# PCB-PAYLOAD_FINAL.net
KiCad netlist of a schematic drawn in EAGLE
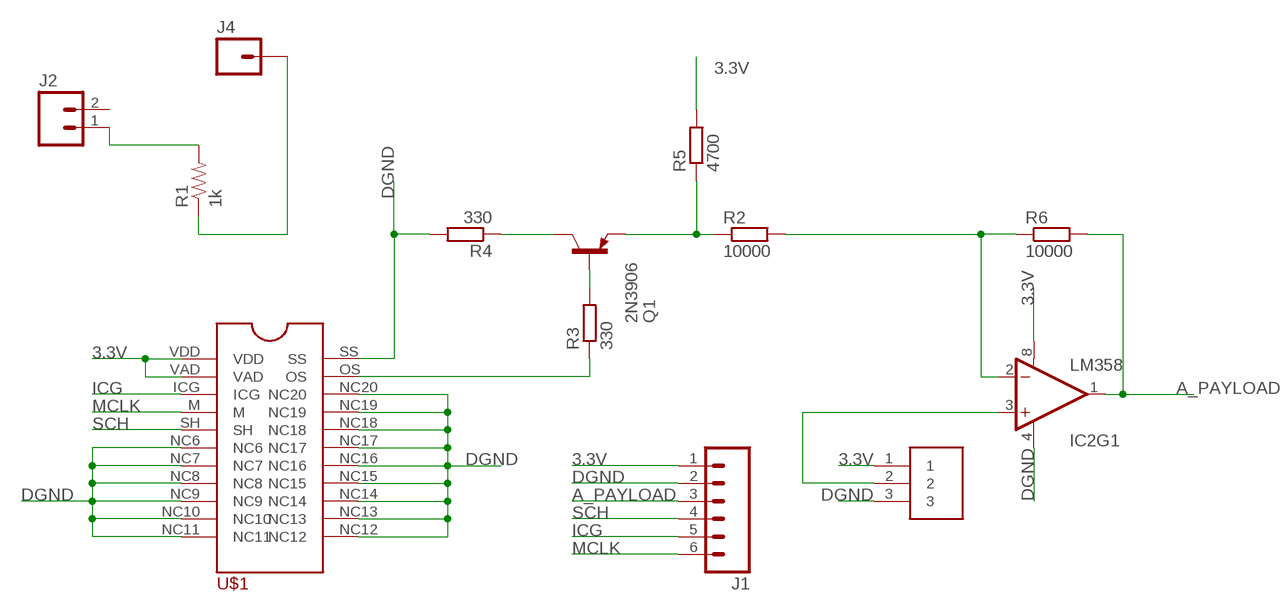
[diagram p0: schematic, sheet 1]

(export (version "E")
  (design (tool "Eeschema 10.0.6"))
  (components
    (comp (ref "IC2")
      (value "LM358")
      (footprint "eagle-import:DIP08")
      (libsource (lib "eagle-import") (part "LM358"))
    )
    (comp (ref "J1")
      (value "M06SILK_FEMALE_PTH")
      (footprint "eagle-import:1X06")
      (libsource (lib "eagle-import") (part "M06SILK_FEMALE_PTH"))
    )
    (comp (ref "J2")
      (value "M02PTH")
      (footprint "eagle-import:1X02")
      (libsource (lib "eagle-import") (part "M02PTH"))
    )
    (comp (ref "J4")
      (value "M01PTH")
      (footprint "eagle-import:1X01")
      (libsource (lib "eagle-import") (part "M01PTH"))
    )
    (comp (ref "Q1")
      (value "2N3906")
      (footprint "eagle-import:TO92")
      (libsource (lib "eagle-import") (part "2N3906"))
    )
    (comp (ref "R1")
      (value "1k")
      (footprint "eagle-import:AXIAL-0.3")
      (libsource (lib "eagle-import") (part "1KOHM-1/4W-5%(PTH)"))
    )
    (comp (ref "R2")
      (value "10000")
      (footprint "eagle-import:0204_5")
      (libsource (lib "eagle-import") (part "R-EU_0204/5"))
    )
    (comp (ref "R3")
      (value "330")
      (footprint "eagle-import:0204_5")
      (libsource (lib "eagle-import") (part "R-EU_0204/5"))
    )
    (comp (ref "R4")
      (value "330")
      (footprint "eagle-import:0204_5")
      (libsource (lib "eagle-import") (part "R-EU_0204/5"))
    )
    (comp (ref "R5")
      (value "4700")
      (footprint "eagle-import:0204_5")
      (libsource (lib "eagle-import") (part "R-EU_0204/5"))
    )
    (comp (ref "R6")
      (value "10000")
      (footprint "eagle-import:0204_5")
      (libsource (lib "eagle-import") (part "R-EU_0204/5"))
    )
    (comp (ref "U$1")
      (value "CCD")
      (footprint "eagle-import:CCD")
      (libsource (lib "eagle-import") (part "CCD"))
    )
    (comp (ref "U$2")
      (value "TRIMPOT_DEVICE")
      (footprint "eagle-import:TRIM_POT_PACKAGE")
      (libsource (lib "eagle-import") (part "TRIMPOT_DEVICE"))
    )
  )
  (nets
    (net (code "1") (name "/3.3V") (class "Default")
      (node (ref "IC2") (pin "8") (pinfunction "V+_8") (pintype "power_in"))
      (node (ref "J1") (pin "1") (pinfunction "1_1") (pintype "passive"))
      (node (ref "R5") (pin "2") (pinfunction "2_2") (pintype "passive"))
      (node (ref "U$1") (pin "VAD") (pinfunction "VAD_VAD") (pintype "bidirectional"))
      (node (ref "U$1") (pin "VDD") (pinfunction "VDD_VDD") (pintype "bidirectional"))
      (node (ref "U$2") (pin "1") (pinfunction "1_1") (pintype "bidirectional"))
    )
    (net (code "2") (name "/A_PAYLOAD") (class "Default")
      (node (ref "IC2") (pin "1") (pinfunction "OUT_1") (pintype "output"))
      (node (ref "J1") (pin "3") (pinfunction "3_3") (pintype "passive"))
      (node (ref "R6") (pin "2") (pinfunction "2_2") (pintype "passive"))
    )
    (net (code "3") (name "/DGND") (class "Default")
      (node (ref "IC2") (pin "4") (pinfunction "V-_4") (pintype "power_in"))
      (node (ref "J1") (pin "2") (pinfunction "2_2") (pintype "passive"))
      (node (ref "R4") (pin "2") (pinfunction "2_2") (pintype "passive"))
      (node (ref "U$1") (pin "NC10") (pinfunction "NC10_NC10") (pintype "bidirectional"))
      (node (ref "U$1") (pin "NC11") (pinfunction "NC11_NC11") (pintype "bidirectional"))
      (node (ref "U$1") (pin "NC12") (pinfunction "NC12_NC12") (pintype "bidirectional"))
      (node (ref "U$1") (pin "NC13") (pinfunction "NC13_NC13") (pintype "bidirectional"))
      (node (ref "U$1") (pin "NC14") (pinfunction "NC14_NC14") (pintype "bidirectional"))
      (node (ref "U$1") (pin "NC15") (pinfunction "NC15_NC15") (pintype "bidirectional"))
      (node (ref "U$1") (pin "NC16") (pinfunction "NC16_NC16") (pintype "bidirectional"))
      (node (ref "U$1") (pin "NC17") (pinfunction "NC17_NC17") (pintype "bidirectional"))
      (node (ref "U$1") (pin "NC18") (pinfunction "NC18_NC18") (pintype "bidirectional"))
      (node (ref "U$1") (pin "NC19") (pinfunction "NC19_NC19") (pintype "bidirectional"))
      (node (ref "U$1") (pin "NC20") (pinfunction "NC20_NC20") (pintype "bidirectional"))
      (node (ref "U$1") (pin "NC6") (pinfunction "NC6_NC6") (pintype "bidirectional"))
      (node (ref "U$1") (pin "NC7") (pinfunction "NC7_NC7") (pintype "bidirectional"))
      (node (ref "U$1") (pin "NC8") (pinfunction "NC8_NC8") (pintype "bidirectional"))
      (node (ref "U$1") (pin "NC9") (pinfunction "NC9_NC9") (pintype "bidirectional"))
      (node (ref "U$1") (pin "SS") (pinfunction "SS_SS") (pintype "bidirectional"))
      (node (ref "U$2") (pin "3") (pinfunction "3_3") (pintype "bidirectional"))
    )
    (net (code "4") (name "/ICG") (class "Default")
      (node (ref "J1") (pin "5") (pinfunction "5_5") (pintype "passive"))
      (node (ref "U$1") (pin "ICG") (pinfunction "ICG_ICG") (pintype "bidirectional"))
    )
    (net (code "5") (name "/MCLK") (class "Default")
      (node (ref "J1") (pin "6") (pinfunction "6_6") (pintype "passive"))
      (node (ref "U$1") (pin "M") (pinfunction "M_M") (pintype "bidirectional"))
    )
    (net (code "6") (name "/SCH") (class "Default")
      (node (ref "J1") (pin "4") (pinfunction "4_4") (pintype "passive"))
      (node (ref "U$1") (pin "SH") (pinfunction "SH_SH") (pintype "bidirectional"))
    )
    (net (code "7") (name "Net-(IC2A-+IN)") (class "Default")
      (node (ref "IC2") (pin "3") (pinfunction "+IN_3") (pintype "input"))
      (node (ref "U$2") (pin "2") (pinfunction "2_2") (pintype "bidirectional"))
    )
    (net (code "8") (name "Net-(IC2A--IN)") (class "Default")
      (node (ref "IC2") (pin "2") (pinfunction "-IN_2") (pintype "input"))
      (node (ref "R2") (pin "2") (pinfunction "2_2") (pintype "passive"))
      (node (ref "R6") (pin "1") (pinfunction "1_1") (pintype "passive"))
    )
    (net (code "9") (name "Net-(Q1-B)") (class "Default")
      (node (ref "Q1") (pin "2") (pinfunction "B_2") (pintype "passive"))
      (node (ref "R3") (pin "2") (pinfunction "2_2") (pintype "passive"))
    )
    (net (code "10") (name "Net-(Q1-C)") (class "Default")
      (node (ref "Q1") (pin "1") (pinfunction "C_1") (pintype "passive"))
      (node (ref "R4") (pin "1") (pinfunction "1_1") (pintype "passive"))
    )
    (net (code "11") (name "Net-(Q1-E)") (class "Default")
      (node (ref "Q1") (pin "3") (pinfunction "E_3") (pintype "passive"))
      (node (ref "R2") (pin "1") (pinfunction "1_1") (pintype "passive"))
      (node (ref "R5") (pin "1") (pinfunction "1_1") (pintype "passive"))
    )
    (net (code "12") (name "Net-(R1-1)") (class "Default")
      (node (ref "J4") (pin "1") (pinfunction "1_1") (pintype "passive"))
      (node (ref "R1") (pin "P$1") (pinfunction "1_P$1") (pintype "passive"))
    )
    (net (code "13") (name "Net-(R1-2)") (class "Default")
      (node (ref "J2") (pin "1") (pinfunction "1_1") (pintype "passive"))
      (node (ref "R1") (pin "P$2") (pinfunction "2_P$2") (pintype "passive"))
    )
    (net (code "14") (name "Net-(R3-Pad1)") (class "Default")
      (node (ref "R3") (pin "1") (pinfunction "1_1") (pintype "passive"))
      (node (ref "U$1") (pin "OS") (pinfunction "OS_OS") (pintype "bidirectional"))
    )
    (net (code "15") (name "unconnected-(J2-Pad2)") (class "Default")
      (node (ref "J2") (pin "2") (pinfunction "2_2") (pintype "passive"))
    )
  )
)
